# CommsTestBoard.net
KiCad netlist of a schematic drawn in EAGLE
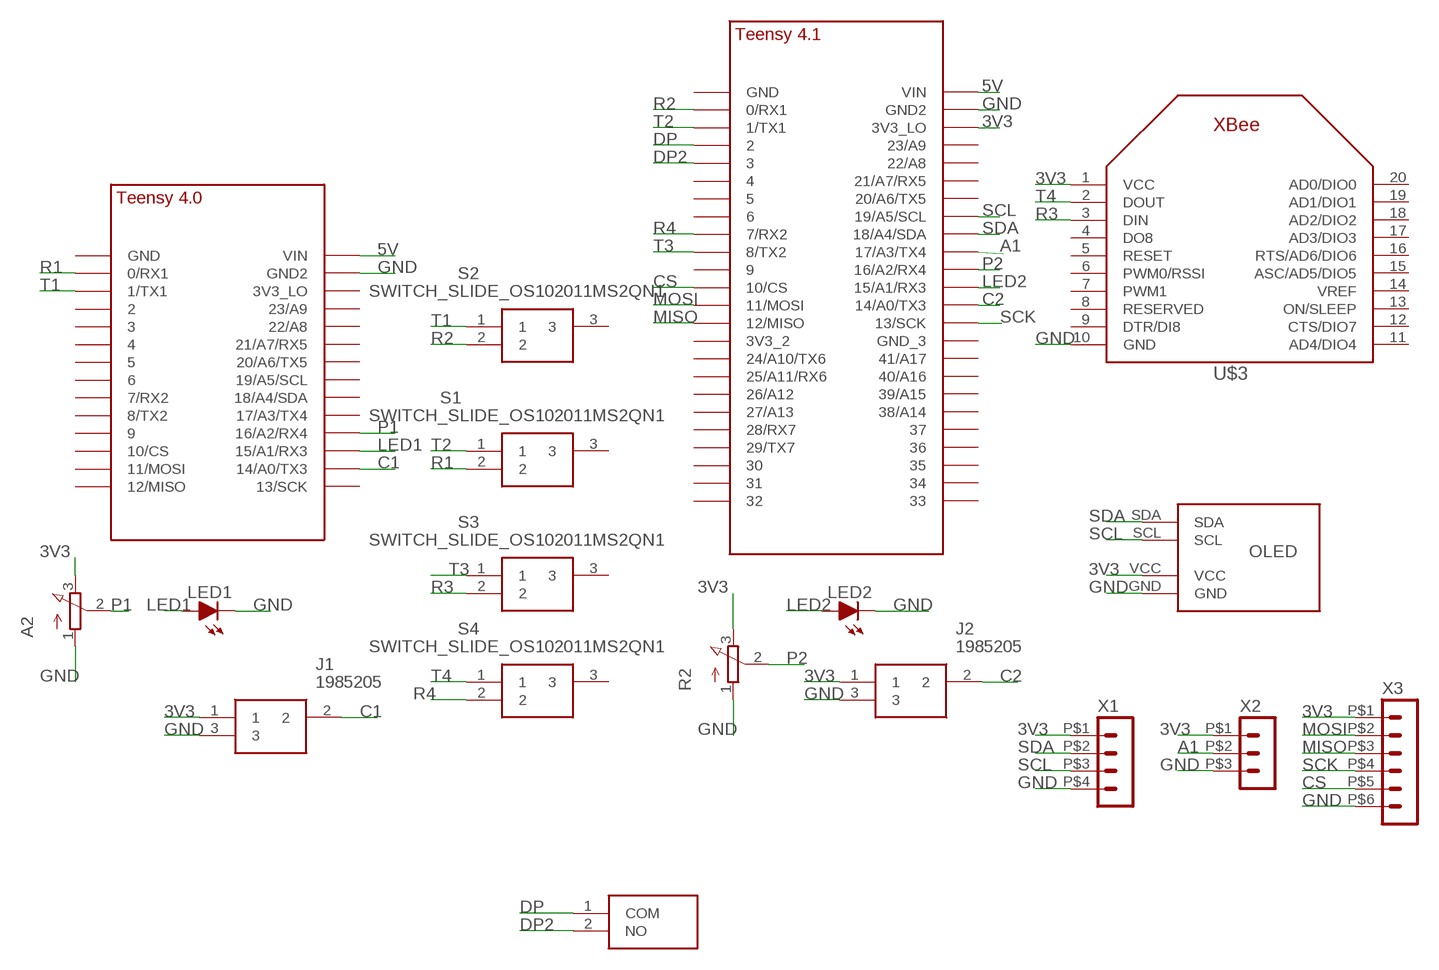
[diagram p0: schematic, sheet 1]

(export (version "E")
  (design (tool "Eeschema 10.0.6"))
  (components
    (comp (ref "A2")
      (value "POTENTIOMETER")
      (footprint "eagle-import:3RP_1610N")
      (libsource (lib "eagle-import") (part "POTENTIOMETER"))
    )
    (comp (ref "J1")
      (value "1985205")
      (footprint "eagle-import:1985205")
      (fields (field (name "MOUSER_PART_NUMBER") "651-1985205"))
      (libsource (lib "eagle-import") (part "1985205"))
    )
    (comp (ref "J2")
      (value "1985205")
      (footprint "eagle-import:1985205")
      (fields (field (name "MOUSER_PART_NUMBER") "651-1985205"))
      (libsource (lib "eagle-import") (part "1985205"))
    )
    (comp (ref "LED1")
      (value "LED-5MM")
      (footprint "eagle-import:LED-5MM")
      (libsource (lib "eagle-import") (part "LED-5MM"))
    )
    (comp (ref "LED2")
      (value "LED-5MM")
      (footprint "eagle-import:LED-5MM")
      (libsource (lib "eagle-import") (part "LED-5MM"))
    )
    (comp (ref "R2")
      (value "POTENTIOMETER")
      (footprint "eagle-import:3RP_1610N")
      (libsource (lib "eagle-import") (part "POTENTIOMETER"))
    )
    (comp (ref "S1")
      (value "SWITCH_SLIDE_OS102011MS2QN1")
      (footprint "eagle-import:OS102011MA1QN1")
      (fields
        (field (name "ARROW_PART_NUMBER") "OS102011MS2QN1")
        (field (name "MOUSER_PART_NUMBER") "611-OS102011MS2QN1")
      )
      (libsource (lib "eagle-import") (part "SWITCH_SLIDE_OS102011MS2QN1"))
    )
    (comp (ref "S2")
      (value "SWITCH_SLIDE_OS102011MS2QN1")
      (footprint "eagle-import:OS102011MA1QN1")
      (fields
        (field (name "ARROW_PART_NUMBER") "OS102011MS2QN1")
        (field (name "MOUSER_PART_NUMBER") "611-OS102011MS2QN1")
      )
      (libsource (lib "eagle-import") (part "SWITCH_SLIDE_OS102011MS2QN1"))
    )
    (comp (ref "S3")
      (value "SWITCH_SLIDE_OS102011MS2QN1")
      (footprint "eagle-import:OS102011MA1QN1")
      (fields
        (field (name "ARROW_PART_NUMBER") "OS102011MS2QN1")
        (field (name "MOUSER_PART_NUMBER") "611-OS102011MS2QN1")
      )
      (libsource (lib "eagle-import") (part "SWITCH_SLIDE_OS102011MS2QN1"))
    )
    (comp (ref "S4")
      (value "SWITCH_SLIDE_OS102011MS2QN1")
      (footprint "eagle-import:OS102011MA1QN1")
      (fields
        (field (name "ARROW_PART_NUMBER") "OS102011MS2QN1")
        (field (name "MOUSER_PART_NUMBER") "611-OS102011MS2QN1")
      )
      (libsource (lib "eagle-import") (part "SWITCH_SLIDE_OS102011MS2QN1"))
    )
    (comp (ref "S5")
      (value "PTS636_SL50_LFS")
      (footprint "eagle-import:PTS636SL50LFS")
      (fields
        (field (name "ARROW_PART_NUMBER") "PTS636 SL50 LFS")
        (field (name "MOUSER_PART_NUMBER") "611-PTS636SL50LFS")
      )
      (libsource (lib "eagle-import") (part "PTS636_SL50_LFS"))
    )
    (comp (ref "U$1")
      (value "TEENSY_4.0_SIMPLE")
      (footprint "eagle-import:TEENSY_4.0_SIMPLE")
      (libsource (lib "eagle-import") (part "TEENSY_4.0_SIMPLE"))
    )
    (comp (ref "U$2")
      (value "TEENSY_4.1_SIMPLE")
      (footprint "eagle-import:TEENSY_4.1_SIMPLE")
      (libsource (lib "eagle-import") (part "TEENSY_4.1_SIMPLE"))
    )
    (comp (ref "U$3")
      (value "XBEE")
      (footprint "eagle-import:XBEE")
      (libsource (lib "eagle-import") (part "XBEE"))
    )
    (comp (ref "U$4")
      (value "OLED_SSD1306")
      (footprint "eagle-import:OLED_SSD1306")
      (libsource (lib "eagle-import") (part "OLED_SSD1306"))
    )
    (comp (ref "X1")
      (value "HEADER_POS4_43045-0401")
      (footprint "eagle-import:43045-0400")
      (libsource (lib "eagle-import") (part "HEADER_POS4_?43045-0401"))
    )
    (comp (ref "X2")
      (value "HEADER_POS3_43650-0300")
      (footprint "eagle-import:43650-0300")
      (libsource (lib "eagle-import") (part "HEADER_POS3_?43650-0300"))
    )
    (comp (ref "X3")
      (value "HEADER_POS6_43045-0600")
      (footprint "eagle-import:43045-0600")
      (libsource (lib "eagle-import") (part "HEADER_POS6_?43045-0600"))
    )
  )
  (nets
    (net (code "1") (name "/3V3") (class "Default")
      (node (ref "A2") (pin "3") (pinfunction "E_3") (pintype "passive"))
      (node (ref "J1") (pin "1") (pinfunction "1_1") (pintype "bidirectional"))
      (node (ref "J2") (pin "1") (pinfunction "1_1") (pintype "bidirectional"))
      (node (ref "R2") (pin "3") (pinfunction "E_3") (pintype "passive"))
      (node (ref "U$2") (pin "3V3_LO") (pinfunction "3V3_LO_3V3_LO") (pintype "bidirectional"))
      (node (ref "U$3") (pin "1") (pinfunction "VCC_1") (pintype "power_in"))
      (node (ref "U$4") (pin "VCC") (pinfunction "VCC_VCC") (pintype "bidirectional"))
      (node (ref "X1") (pin "P$1") (pinfunction "1_P$1") (pintype "passive"))
      (node (ref "X2") (pin "P$1") (pinfunction "1_P$1") (pintype "passive"))
      (node (ref "X3") (pin "P$1") (pinfunction "1_P$1") (pintype "passive"))
    )
    (net (code "2") (name "/5V") (class "Default")
      (node (ref "U$1") (pin "VIN") (pinfunction "VIN_VIN") (pintype "bidirectional"))
      (node (ref "U$2") (pin "VIN") (pinfunction "VIN_VIN") (pintype "bidirectional"))
    )
    (net (code "3") (name "/A1") (class "Default")
      (node (ref "U$2") (pin "17/A3") (pinfunction "17/A3/TX4_17/A3") (pintype "bidirectional"))
      (node (ref "X2") (pin "P$2") (pinfunction "2_P$2") (pintype "passive"))
    )
    (net (code "4") (name "/C1") (class "Default")
      (node (ref "J1") (pin "2") (pinfunction "2_2") (pintype "bidirectional"))
      (node (ref "U$1") (pin "14/A0") (pinfunction "14/A0/TX3_14/A0") (pintype "bidirectional"))
    )
    (net (code "5") (name "/C2") (class "Default")
      (node (ref "J2") (pin "2") (pinfunction "2_2") (pintype "bidirectional"))
      (node (ref "U$2") (pin "14/A0") (pinfunction "14/A0/TX3_14/A0") (pintype "bidirectional"))
    )
    (net (code "6") (name "/CS") (class "Default")
      (node (ref "U$2") (pin "10/CS") (pinfunction "10/CS_10/CS") (pintype "bidirectional"))
      (node (ref "X3") (pin "P$5") (pinfunction "5_P$5") (pintype "passive"))
    )
    (net (code "7") (name "/DP") (class "Default")
      (node (ref "S5") (pin "1") (pinfunction "COM_1") (pintype "bidirectional"))
      (node (ref "U$2") (pin "2") (pinfunction "2_2") (pintype "bidirectional"))
    )
    (net (code "8") (name "/DP2") (class "Default")
      (node (ref "S5") (pin "2") (pinfunction "NO_2") (pintype "bidirectional"))
      (node (ref "U$2") (pin "3/CANTX") (pinfunction "3_3/CANTX") (pintype "bidirectional"))
    )
    (net (code "9") (name "/GND") (class "Default")
      (node (ref "A2") (pin "1") (pinfunction "A_1") (pintype "passive"))
      (node (ref "J1") (pin "3") (pinfunction "3_3") (pintype "bidirectional"))
      (node (ref "J2") (pin "3") (pinfunction "3_3") (pintype "bidirectional"))
      (node (ref "LED1") (pin "K") (pinfunction "C_K") (pintype "passive"))
      (node (ref "LED2") (pin "K") (pinfunction "C_K") (pintype "passive"))
      (node (ref "R2") (pin "1") (pinfunction "A_1") (pintype "passive"))
      (node (ref "U$1") (pin "GND2") (pinfunction "GND2_GND2") (pintype "bidirectional"))
      (node (ref "U$2") (pin "GND2") (pinfunction "GND2_GND2") (pintype "bidirectional"))
      (node (ref "U$3") (pin "10") (pinfunction "GND_10") (pintype "power_in"))
      (node (ref "U$4") (pin "GND") (pinfunction "GND_GND") (pintype "bidirectional"))
      (node (ref "X1") (pin "P$4") (pinfunction "4_P$4") (pintype "passive"))
      (node (ref "X2") (pin "P$3") (pinfunction "3_P$3") (pintype "passive"))
      (node (ref "X3") (pin "P$6") (pinfunction "6_P$6") (pintype "passive"))
    )
    (net (code "10") (name "/LED1") (class "Default")
      (node (ref "LED1") (pin "A") (pinfunction "A_A") (pintype "passive"))
      (node (ref "U$1") (pin "15/A1") (pinfunction "15/A1/RX3_15/A1") (pintype "bidirectional"))
    )
    (net (code "11") (name "/LED2") (class "Default")
      (node (ref "LED2") (pin "A") (pinfunction "A_A") (pintype "passive"))
      (node (ref "U$2") (pin "15/A1") (pinfunction "15/A1/RX3_15/A1") (pintype "bidirectional"))
    )
    (net (code "12") (name "/MISO") (class "Default")
      (node (ref "U$2") (pin "12/MISO") (pinfunction "12/MISO_12/MISO") (pintype "bidirectional"))
      (node (ref "X3") (pin "P$3") (pinfunction "3_P$3") (pintype "passive"))
    )
    (net (code "13") (name "/MOSI") (class "Default")
      (node (ref "U$2") (pin "11/MOSI") (pinfunction "11/MOSI_11/MOSI") (pintype "bidirectional"))
      (node (ref "X3") (pin "P$2") (pinfunction "2_P$2") (pintype "passive"))
    )
    (net (code "14") (name "/P1") (class "Default")
      (node (ref "A2") (pin "2") (pinfunction "S_2") (pintype "passive"))
      (node (ref "U$1") (pin "16/A2") (pinfunction "16/A2/RX4_16/A2") (pintype "bidirectional"))
    )
    (net (code "15") (name "/P2") (class "Default")
      (node (ref "R2") (pin "2") (pinfunction "S_2") (pintype "passive"))
      (node (ref "U$2") (pin "16/A2") (pinfunction "16/A2/RX4_16/A2") (pintype "bidirectional"))
    )
    (net (code "16") (name "/R1") (class "Default")
      (node (ref "S1") (pin "2") (pinfunction "2_2") (pintype "bidirectional"))
      (node (ref "U$1") (pin "0/RX") (pinfunction "0/RX1_0/RX") (pintype "bidirectional"))
    )
    (net (code "17") (name "/R2") (class "Default")
      (node (ref "S2") (pin "2") (pinfunction "2_2") (pintype "bidirectional"))
      (node (ref "U$2") (pin "0/RX") (pinfunction "0/RX1_0/RX") (pintype "bidirectional"))
    )
    (net (code "18") (name "/R3") (class "Default")
      (node (ref "S3") (pin "2") (pinfunction "2_2") (pintype "bidirectional"))
      (node (ref "U$3") (pin "3") (pinfunction "DIN_3") (pintype "input"))
    )
    (net (code "19") (name "/R4") (class "Default")
      (node (ref "S4") (pin "2") (pinfunction "2_2") (pintype "bidirectional"))
      (node (ref "U$2") (pin "7") (pinfunction "7/RX2_7") (pintype "bidirectional"))
    )
    (net (code "20") (name "/SCK") (class "Default")
      (node (ref "U$2") (pin "13/SCK") (pinfunction "13/SCK_13/SCK") (pintype "bidirectional"))
      (node (ref "X3") (pin "P$4") (pinfunction "4_P$4") (pintype "passive"))
    )
    (net (code "21") (name "/SCL") (class "Default")
      (node (ref "U$2") (pin "19/A5/SCL") (pinfunction "19/A5/SCL_19/A5/SCL") (pintype "bidirectional"))
      (node (ref "U$4") (pin "SCL") (pinfunction "SCL_SCL") (pintype "bidirectional"))
      (node (ref "X1") (pin "P$3") (pinfunction "3_P$3") (pintype "passive"))
    )
    (net (code "22") (name "/SDA") (class "Default")
      (node (ref "U$2") (pin "18/A4/SDA") (pinfunction "18/A4/SDA_18/A4/SDA") (pintype "bidirectional"))
      (node (ref "U$4") (pin "SDA") (pinfunction "SDA_SDA") (pintype "bidirectional"))
      (node (ref "X1") (pin "P$2") (pinfunction "2_P$2") (pintype "passive"))
    )
    (net (code "23") (name "/T1") (class "Default")
      (node (ref "S2") (pin "1") (pinfunction "1_1") (pintype "bidirectional"))
      (node (ref "U$1") (pin "1/TX") (pinfunction "1/TX1_1/TX") (pintype "bidirectional"))
    )
    (net (code "24") (name "/T2") (class "Default")
      (node (ref "S1") (pin "1") (pinfunction "1_1") (pintype "bidirectional"))
      (node (ref "U$2") (pin "1/TX") (pinfunction "1/TX1_1/TX") (pintype "bidirectional"))
    )
    (net (code "25") (name "/T3") (class "Default")
      (node (ref "S3") (pin "1") (pinfunction "1_1") (pintype "bidirectional"))
      (node (ref "U$2") (pin "8") (pinfunction "8/TX2_8") (pintype "bidirectional"))
    )
    (net (code "26") (name "/T4") (class "Default")
      (node (ref "S4") (pin "1") (pinfunction "1_1") (pintype "bidirectional"))
      (node (ref "U$3") (pin "2") (pinfunction "DOUT_2") (pintype "output"))
    )
    (net (code "27") (name "unconnected-(S1-Pad3)") (class "Default")
      (node (ref "S1") (pin "3") (pinfunction "3_3") (pintype "bidirectional"))
    )
    (net (code "28") (name "unconnected-(S2-Pad3)") (class "Default")
      (node (ref "S2") (pin "3") (pinfunction "3_3") (pintype "bidirectional"))
    )
    (net (code "29") (name "unconnected-(S3-Pad3)") (class "Default")
      (node (ref "S3") (pin "3") (pinfunction "3_3") (pintype "bidirectional"))
    )
    (net (code "30") (name "unconnected-(S4-Pad3)") (class "Default")
      (node (ref "S4") (pin "3") (pinfunction "3_3") (pintype "bidirectional"))
    )
    (net (code "31") (name "unconnected-(U$1-3-Pad3{slash}CANTX)") (class "Default")
      (node (ref "U$1") (pin "3/CANTX") (pinfunction "3_3/CANTX") (pintype "bidirectional"))
    )
    (net (code "32") (name "unconnected-(U$1-4-Pad4{slash}CANRX)") (class "Default")
      (node (ref "U$1") (pin "4/CANRX") (pinfunction "4_4/CANRX") (pintype "bidirectional"))
    )
    (net (code "33") (name "unconnected-(U$1-7{slash}RX2-Pad7)") (class "Default")
      (node (ref "U$1") (pin "7") (pinfunction "7/RX2_7") (pintype "bidirectional"))
    )
    (net (code "34") (name "unconnected-(U$1-8{slash}TX2-Pad8)") (class "Default")
      (node (ref "U$1") (pin "8") (pinfunction "8/TX2_8") (pintype "bidirectional"))
    )
    (net (code "35") (name "unconnected-(U$1-9-Pad9{slash}CS)") (class "Default")
      (node (ref "U$1") (pin "9/CS") (pinfunction "9_9/CS") (pintype "bidirectional"))
    )
    (net (code "36") (name "unconnected-(U$1-17{slash}A3{slash}TX4-Pad17{slash}A3)") (class "Default")
      (node (ref "U$1") (pin "17/A3") (pinfunction "17/A3/TX4_17/A3") (pintype "bidirectional"))
    )
    (net (code "37") (name "unconnected-(U$1-20{slash}A6{slash}TX5-Pad20{slash}A6)") (class "Default")
      (node (ref "U$1") (pin "20/A6") (pinfunction "20/A6/TX5_20/A6") (pintype "bidirectional"))
    )
    (net (code "38") (name "unconnected-(U$1-21{slash}A7{slash}RX5-Pad21{slash}A7)") (class "Default")
      (node (ref "U$1") (pin "21/A7") (pinfunction "21/A7/RX5_21/A7") (pintype "bidirectional"))
    )
    (net (code "39") (name "unconnected-(U$1-Pad2)") (class "Default")
      (node (ref "U$1") (pin "2") (pinfunction "2_2") (pintype "bidirectional"))
    )
    (net (code "40") (name "unconnected-(U$1-Pad3V3_LO)") (class "Default")
      (node (ref "U$1") (pin "3V3_LO") (pinfunction "3V3_LO_3V3_LO") (pintype "bidirectional"))
    )
    (net (code "41") (name "unconnected-(U$1-Pad5)") (class "Default")
      (node (ref "U$1") (pin "5") (pinfunction "5_5") (pintype "bidirectional"))
    )
    (net (code "42") (name "unconnected-(U$1-Pad6)") (class "Default")
      (node (ref "U$1") (pin "6") (pinfunction "6_6") (pintype "bidirectional"))
    )
    (net (code "43") (name "unconnected-(U$1-Pad10{slash}CS)") (class "Default")
      (node (ref "U$1") (pin "10/CS") (pinfunction "10/CS_10/CS") (pintype "bidirectional"))
    )
    (net (code "44") (name "unconnected-(U$1-Pad11{slash}MOSI)") (class "Default")
      (node (ref "U$1") (pin "11/MOSI") (pinfunction "11/MOSI_11/MOSI") (pintype "bidirectional"))
    )
    (net (code "45") (name "unconnected-(U$1-Pad12{slash}MISO)") (class "Default")
      (node (ref "U$1") (pin "12/MISO") (pinfunction "12/MISO_12/MISO") (pintype "bidirectional"))
    )
    (net (code "46") (name "unconnected-(U$1-Pad13{slash}SCK)") (class "Default")
      (node (ref "U$1") (pin "13/SCK") (pinfunction "13/SCK_13/SCK") (pintype "bidirectional"))
    )
    (net (code "47") (name "unconnected-(U$1-Pad18{slash}A4{slash}SDA)") (class "Default")
      (node (ref "U$1") (pin "18/A4/SDA") (pinfunction "18/A4/SDA_18/A4/SDA") (pintype "bidirectional"))
    )
    (net (code "48") (name "unconnected-(U$1-Pad19{slash}A5{slash}SCL)") (class "Default")
      (node (ref "U$1") (pin "19/A5/SCL") (pinfunction "19/A5/SCL_19/A5/SCL") (pintype "bidirectional"))
    )
    (net (code "49") (name "unconnected-(U$1-Pad22{slash}A8)") (class "Default")
      (node (ref "U$1") (pin "22/A8") (pinfunction "22/A8_22/A8") (pintype "bidirectional"))
    )
    (net (code "50") (name "unconnected-(U$1-Pad23{slash}A9)") (class "Default")
      (node (ref "U$1") (pin "23/A9") (pinfunction "23/A9_23/A9") (pintype "bidirectional"))
    )
    (net (code "51") (name "unconnected-(U$1-PadGND)") (class "Default")
      (node (ref "U$1") (pin "GND") (pinfunction "GND_GND") (pintype "bidirectional"))
    )
    (net (code "52") (name "unconnected-(U$2-4-Pad4{slash}CANRX)") (class "Default")
      (node (ref "U$2") (pin "4/CANRX") (pinfunction "4_4/CANRX") (pintype "bidirectional"))
    )
    (net (code "53") (name "unconnected-(U$2-9-Pad9{slash}CS)") (class "Default")
      (node (ref "U$2") (pin "9/CS") (pinfunction "9_9/CS") (pintype "bidirectional"))
    )
    (net (code "54") (name "unconnected-(U$2-20{slash}A6{slash}TX5-Pad20{slash}A6)") (class "Default")
      (node (ref "U$2") (pin "20/A6") (pinfunction "20/A6/TX5_20/A6") (pintype "bidirectional"))
    )
    (net (code "55") (name "unconnected-(U$2-21{slash}A7{slash}RX5-Pad21{slash}A7)") (class "Default")
      (node (ref "U$2") (pin "21/A7") (pinfunction "21/A7/RX5_21/A7") (pintype "bidirectional"))
    )
    (net (code "56") (name "unconnected-(U$2-24{slash}A10{slash}TX6-Pad24{slash}A10)") (class "Default")
      (node (ref "U$2") (pin "24/A10") (pinfunction "24/A10/TX6_24/A10") (pintype "bidirectional"))
    )
    (net (code "57") (name "unconnected-(U$2-25{slash}A11{slash}RX6-Pad25{slash}A11)") (class "Default")
      (node (ref "U$2") (pin "25/A11") (pinfunction "25/A11/RX6_25/A11") (pintype "bidirectional"))
    )
    (net (code "58") (name "unconnected-(U$2-28{slash}RX7-Pad28)") (class "Default")
      (node (ref "U$2") (pin "28") (pinfunction "28/RX7_28") (pintype "bidirectional"))
    )
    (net (code "59") (name "unconnected-(U$2-29{slash}TX7-Pad29)") (class "Default")
      (node (ref "U$2") (pin "29") (pinfunction "29/TX7_29") (pintype "bidirectional"))
    )
    (net (code "60") (name "unconnected-(U$2-GND_3-PadGND3)") (class "Default")
      (node (ref "U$2") (pin "GND3") (pinfunction "GND_3_GND3") (pintype "bidirectional"))
    )
    (net (code "61") (name "unconnected-(U$2-Pad3V3_2)") (class "Default")
      (node (ref "U$2") (pin "3V3_2") (pinfunction "3V3_2_3V3_2") (pintype "bidirectional"))
    )
    (net (code "62") (name "unconnected-(U$2-Pad5)") (class "Default")
      (node (ref "U$2") (pin "5") (pinfunction "5_5") (pintype "bidirectional"))
    )
    (net (code "63") (name "unconnected-(U$2-Pad6)") (class "Default")
      (node (ref "U$2") (pin "6") (pinfunction "6_6") (pintype "bidirectional"))
    )
    (net (code "64") (name "unconnected-(U$2-Pad22{slash}A8)") (class "Default")
      (node (ref "U$2") (pin "22/A8") (pinfunction "22/A8_22/A8") (pintype "bidirectional"))
    )
    (net (code "65") (name "unconnected-(U$2-Pad23{slash}A9)") (class "Default")
      (node (ref "U$2") (pin "23/A9") (pinfunction "23/A9_23/A9") (pintype "bidirectional"))
    )
    (net (code "66") (name "unconnected-(U$2-Pad26{slash}A12)") (class "Default")
      (node (ref "U$2") (pin "26/A12") (pinfunction "26/A12_26/A12") (pintype "bidirectional"))
    )
    (net (code "67") (name "unconnected-(U$2-Pad27{slash}A13)") (class "Default")
      (node (ref "U$2") (pin "27/A13") (pinfunction "27/A13_27/A13") (pintype "bidirectional"))
    )
    (net (code "68") (name "unconnected-(U$2-Pad30)") (class "Default")
      (node (ref "U$2") (pin "30") (pinfunction "30_30") (pintype "bidirectional"))
    )
    (net (code "69") (name "unconnected-(U$2-Pad31)") (class "Default")
      (node (ref "U$2") (pin "31") (pinfunction "31_31") (pintype "bidirectional"))
    )
    (net (code "70") (name "unconnected-(U$2-Pad32)") (class "Default")
      (node (ref "U$2") (pin "32") (pinfunction "32_32") (pintype "bidirectional"))
    )
    (net (code "71") (name "unconnected-(U$2-Pad33)") (class "Default")
      (node (ref "U$2") (pin "33") (pinfunction "33_33") (pintype "bidirectional"))
    )
    (net (code "72") (name "unconnected-(U$2-Pad34)") (class "Default")
      (node (ref "U$2") (pin "34") (pinfunction "34_34") (pintype "bidirectional"))
    )
    (net (code "73") (name "unconnected-(U$2-Pad35)") (class "Default")
      (node (ref "U$2") (pin "35") (pinfunction "35_35") (pintype "bidirectional"))
    )
    (net (code "74") (name "unconnected-(U$2-Pad36)") (class "Default")
      (node (ref "U$2") (pin "36") (pinfunction "36_36") (pintype "bidirectional"))
    )
    (net (code "75") (name "unconnected-(U$2-Pad37)") (class "Default")
      (node (ref "U$2") (pin "37") (pinfunction "37_37") (pintype "bidirectional"))
    )
    (net (code "76") (name "unconnected-(U$2-Pad38{slash}A14)") (class "Default")
      (node (ref "U$2") (pin "38/A14") (pinfunction "38/A14_38/A14") (pintype "bidirectional"))
    )
    (net (code "77") (name "unconnected-(U$2-Pad39{slash}A15)") (class "Default")
      (node (ref "U$2") (pin "39/A15") (pinfunction "39/A15_39/A15") (pintype "bidirectional"))
    )
    (net (code "78") (name "unconnected-(U$2-Pad40{slash}A16)") (class "Default")
      (node (ref "U$2") (pin "40/A16") (pinfunction "40/A16_40/A16") (pintype "bidirectional"))
    )
    (net (code "79") (name "unconnected-(U$2-Pad41{slash}A17)") (class "Default")
      (node (ref "U$2") (pin "41/A17") (pinfunction "41/A17_41/A17") (pintype "bidirectional"))
    )
    (net (code "80") (name "unconnected-(U$2-PadGND)") (class "Default")
      (node (ref "U$2") (pin "GND") (pinfunction "GND_GND") (pintype "bidirectional"))
    )
    (net (code "81") (name "unconnected-(U$3-AD0{slash}DIO0-Pad20)") (class "Default")
      (node (ref "U$3") (pin "20") (pinfunction "AD0/DIO0_20") (pintype "bidirectional"))
    )
    (net (code "82") (name "unconnected-(U$3-AD1{slash}DIO1-Pad19)") (class "Default")
      (node (ref "U$3") (pin "19") (pinfunction "AD1/DIO1_19") (pintype "bidirectional"))
    )
    (net (code "83") (name "unconnected-(U$3-AD2{slash}DIO2-Pad18)") (class "Default")
      (node (ref "U$3") (pin "18") (pinfunction "AD2/DIO2_18") (pintype "bidirectional"))
    )
    (net (code "84") (name "unconnected-(U$3-AD3{slash}DIO3-Pad17)") (class "Default")
      (node (ref "U$3") (pin "17") (pinfunction "AD3/DIO3_17") (pintype "bidirectional"))
    )
    (net (code "85") (name "unconnected-(U$3-AD4{slash}DIO4-Pad11)") (class "Default")
      (node (ref "U$3") (pin "11") (pinfunction "AD4/DIO4_11") (pintype "bidirectional"))
    )
    (net (code "86") (name "unconnected-(U$3-ASC{slash}AD5{slash}DIO5-Pad15)") (class "Default")
      (node (ref "U$3") (pin "15") (pinfunction "ASC/AD5/DIO5_15") (pintype "bidirectional"))
    )
    (net (code "87") (name "unconnected-(U$3-CTS{slash}DIO7-Pad12)") (class "Default")
      (node (ref "U$3") (pin "12") (pinfunction "CTS/DIO7_12") (pintype "bidirectional"))
    )
    (net (code "88") (name "unconnected-(U$3-DO8-Pad4)") (class "Default")
      (node (ref "U$3") (pin "4") (pinfunction "DO8_4") (pintype "output"))
    )
    (net (code "89") (name "unconnected-(U$3-DTR{slash}DI8-Pad9)") (class "Default")
      (node (ref "U$3") (pin "9") (pinfunction "DTR/DI8_9") (pintype "input"))
    )
    (net (code "90") (name "unconnected-(U$3-ON{slash}SLEEP-Pad13)") (class "Default")
      (node (ref "U$3") (pin "13") (pinfunction "ON/SLEEP_13") (pintype "output"))
    )
    (net (code "91") (name "unconnected-(U$3-PWM0{slash}RSSI-Pad6)") (class "Default")
      (node (ref "U$3") (pin "6") (pinfunction "PWM0/RSSI_6") (pintype "output"))
    )
    (net (code "92") (name "unconnected-(U$3-PWM1-Pad7)") (class "Default")
      (node (ref "U$3") (pin "7") (pinfunction "PWM1_7") (pintype "output"))
    )
    (net (code "93") (name "unconnected-(U$3-RESERVED-Pad8)") (class "Default")
      (node (ref "U$3") (pin "8") (pinfunction "RESERVED_8") (pintype "no_connect"))
    )
    (net (code "94") (name "unconnected-(U$3-RESET-Pad5)") (class "Default")
      (node (ref "U$3") (pin "5") (pinfunction "RESET_5") (pintype "input"))
    )
    (net (code "95") (name "unconnected-(U$3-RTS{slash}AD6{slash}DIO6-Pad16)") (class "Default")
      (node (ref "U$3") (pin "16") (pinfunction "RTS/AD6/DIO6_16") (pintype "bidirectional"))
    )
    (net (code "96") (name "unconnected-(U$3-VREF-Pad14)") (class "Default")
      (node (ref "U$3") (pin "14") (pinfunction "VREF_14") (pintype "input"))
    )
  )
)
